# embedded.net
KiCad netlist of a schematic drawn in EAGLE
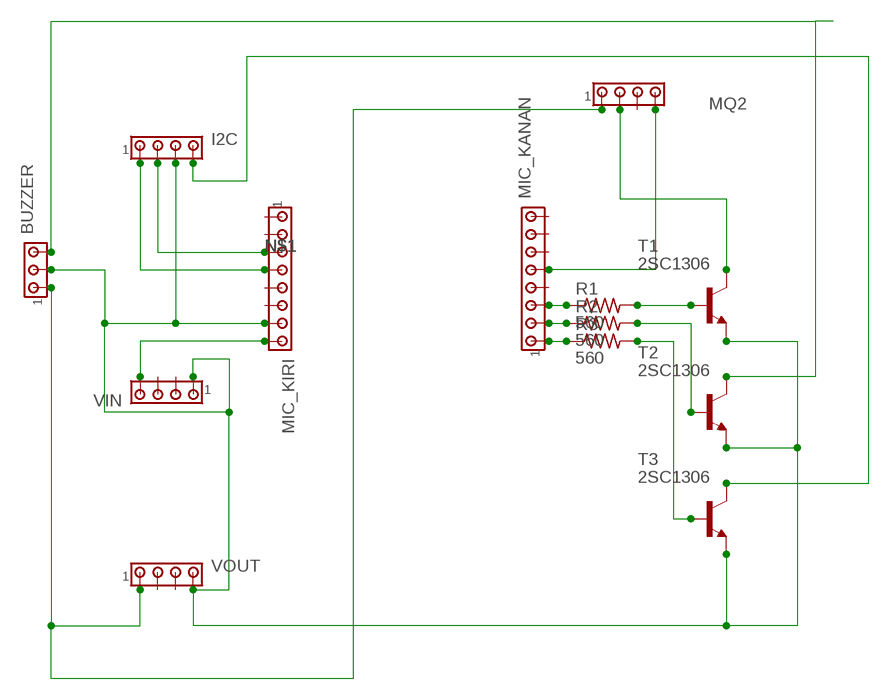
[diagram p0: schematic, sheet 1]

(export (version "E")
  (design (tool "Eeschema 10.0.6"))
  (components
    (comp (ref "BUZZER")
      (value "MTA03-100")
      (footprint "eagle-import:10X03MTA")
      (libsource (lib "eagle-import") (part "MTA03-100"))
    )
    (comp (ref "I2C")
      (value "MTA04-100")
      (footprint "eagle-import:10X04MTA")
      (libsource (lib "eagle-import") (part "MTA04-100"))
    )
    (comp (ref "MIC_KANAN")
      (value "MTA08-100")
      (footprint "eagle-import:10X08MTA")
      (libsource (lib "eagle-import") (part "MTA08-100"))
    )
    (comp (ref "MIC_KIRI")
      (value "MTA08-100")
      (footprint "eagle-import:10X08MTA")
      (libsource (lib "eagle-import") (part "MTA08-100"))
    )
    (comp (ref "MQ2")
      (value "MTA04-100")
      (footprint "eagle-import:10X04MTA")
      (libsource (lib "eagle-import") (part "MTA04-100"))
    )
    (comp (ref "R1")
      (value "560")
      (footprint "eagle-import:0204_7")
      (libsource (lib "eagle-import") (part "R-US_0204/7"))
    )
    (comp (ref "R2")
      (value "560")
      (footprint "eagle-import:0204_7")
      (libsource (lib "eagle-import") (part "R-US_0204/7"))
    )
    (comp (ref "R3")
      (value "560")
      (footprint "eagle-import:0204_7")
      (libsource (lib "eagle-import") (part "R-US_0204/7"))
    )
    (comp (ref "T1")
      (value "2SC1306")
      (footprint "eagle-import:TO220BV")
      (libsource (lib "eagle-import") (part "2SC1306"))
    )
    (comp (ref "T2")
      (value "2SC1306")
      (footprint "eagle-import:TO220BV")
      (libsource (lib "eagle-import") (part "2SC1306"))
    )
    (comp (ref "T3")
      (value "2SC1306")
      (footprint "eagle-import:TO220BV")
      (libsource (lib "eagle-import") (part "2SC1306"))
    )
    (comp (ref "VIN")
      (value "MTA04-100")
      (footprint "eagle-import:10X04MTA")
      (libsource (lib "eagle-import") (part "MTA04-100"))
    )
    (comp (ref "VOUT")
      (value "MTA04-100")
      (footprint "eagle-import:10X04MTA")
      (libsource (lib "eagle-import") (part "MTA04-100"))
    )
  )
  (nets
    (net (code "1") (name "/N$1") (class "Default")
      (node (ref "I2C") (pin "2") (pinfunction "2_2") (pintype "passive"))
      (node (ref "MIC_KIRI") (pin "3") (pinfunction "3_3") (pintype "passive"))
    )
    (net (code "2") (name "Net-(BUZZER-Pad1)") (class "Default")
      (node (ref "BUZZER") (pin "1") (pinfunction "1_1") (pintype "passive"))
      (node (ref "MQ2") (pin "1") (pinfunction "1_1") (pintype "passive"))
      (node (ref "VOUT") (pin "1") (pinfunction "1_1") (pintype "passive"))
    )
    (net (code "3") (name "Net-(I2C-Pad1)") (class "Default")
      (node (ref "I2C") (pin "1") (pinfunction "1_1") (pintype "passive"))
      (node (ref "MIC_KIRI") (pin "4") (pinfunction "4_4") (pintype "passive"))
    )
    (net (code "4") (name "Net-(MIC_KANAN-Pad1)") (class "Default")
      (node (ref "MIC_KANAN") (pin "1") (pinfunction "1_1") (pintype "passive"))
      (node (ref "R3") (pin "1") (pinfunction "1_1") (pintype "passive"))
    )
    (net (code "5") (name "Net-(MIC_KANAN-Pad2)") (class "Default")
      (node (ref "MIC_KANAN") (pin "2") (pinfunction "2_2") (pintype "passive"))
      (node (ref "R2") (pin "1") (pinfunction "1_1") (pintype "passive"))
    )
    (net (code "6") (name "Net-(MIC_KANAN-Pad3)") (class "Default")
      (node (ref "MIC_KANAN") (pin "3") (pinfunction "3_3") (pintype "passive"))
      (node (ref "R1") (pin "1") (pinfunction "1_1") (pintype "passive"))
    )
    (net (code "7") (name "Net-(MIC_KANAN-Pad5)") (class "Default")
      (node (ref "MIC_KANAN") (pin "5") (pinfunction "5_5") (pintype "passive"))
      (node (ref "MQ2") (pin "4") (pinfunction "4_4") (pintype "passive"))
    )
    (net (code "8") (name "Net-(MIC_KIRI-Pad8)") (class "Default")
      (node (ref "MIC_KIRI") (pin "8") (pinfunction "8_8") (pintype "passive"))
      (node (ref "VIN") (pin "4") (pinfunction "4_4") (pintype "passive"))
    )
    (net (code "9") (name "Net-(T1-B)") (class "Default")
      (node (ref "R1") (pin "2") (pinfunction "2_2") (pintype "passive"))
      (node (ref "T1") (pin "1") (pinfunction "B_1") (pintype "passive"))
    )
    (net (code "10") (name "Net-(T1-C)") (class "Default")
      (node (ref "MQ2") (pin "2") (pinfunction "2_2") (pintype "passive"))
      (node (ref "T1") (pin "2") (pinfunction "C_2") (pintype "passive"))
    )
    (net (code "11") (name "Net-(T1-E)") (class "Default")
      (node (ref "BUZZER") (pin "2") (pinfunction "2_2") (pintype "passive"))
      (node (ref "I2C") (pin "3") (pinfunction "3_3") (pintype "passive"))
      (node (ref "MIC_KIRI") (pin "7") (pinfunction "7_7") (pintype "passive"))
      (node (ref "T1") (pin "3") (pinfunction "E_3") (pintype "passive"))
      (node (ref "T2") (pin "3") (pinfunction "E_3") (pintype "passive"))
      (node (ref "T3") (pin "3") (pinfunction "E_3") (pintype "passive"))
      (node (ref "VIN") (pin "1") (pinfunction "1_1") (pintype "passive"))
      (node (ref "VOUT") (pin "4") (pinfunction "4_4") (pintype "passive"))
    )
    (net (code "12") (name "Net-(T2-B)") (class "Default")
      (node (ref "R2") (pin "2") (pinfunction "2_2") (pintype "passive"))
      (node (ref "T2") (pin "1") (pinfunction "B_1") (pintype "passive"))
    )
    (net (code "13") (name "Net-(T2-C)") (class "Default")
      (node (ref "BUZZER") (pin "3") (pinfunction "3_3") (pintype "passive"))
      (node (ref "T2") (pin "2") (pinfunction "C_2") (pintype "passive"))
    )
    (net (code "14") (name "Net-(T3-B)") (class "Default")
      (node (ref "R3") (pin "2") (pinfunction "2_2") (pintype "passive"))
      (node (ref "T3") (pin "1") (pinfunction "B_1") (pintype "passive"))
    )
    (net (code "15") (name "Net-(T3-C)") (class "Default")
      (node (ref "I2C") (pin "4") (pinfunction "4_4") (pintype "passive"))
      (node (ref "T3") (pin "2") (pinfunction "C_2") (pintype "passive"))
    )
    (net (code "16") (name "unconnected-(MIC_KANAN-Pad4)") (class "Default")
      (node (ref "MIC_KANAN") (pin "4") (pinfunction "4_4") (pintype "passive"))
    )
    (net (code "17") (name "unconnected-(MIC_KANAN-Pad6)") (class "Default")
      (node (ref "MIC_KANAN") (pin "6") (pinfunction "6_6") (pintype "passive"))
    )
    (net (code "18") (name "unconnected-(MIC_KANAN-Pad7)") (class "Default")
      (node (ref "MIC_KANAN") (pin "7") (pinfunction "7_7") (pintype "passive"))
    )
    (net (code "19") (name "unconnected-(MIC_KANAN-Pad8)") (class "Default")
      (node (ref "MIC_KANAN") (pin "8") (pinfunction "8_8") (pintype "passive"))
    )
    (net (code "20") (name "unconnected-(MIC_KIRI-Pad1)") (class "Default")
      (node (ref "MIC_KIRI") (pin "1") (pinfunction "1_1") (pintype "passive"))
    )
    (net (code "21") (name "unconnected-(MIC_KIRI-Pad2)") (class "Default")
      (node (ref "MIC_KIRI") (pin "2") (pinfunction "2_2") (pintype "passive"))
    )
    (net (code "22") (name "unconnected-(MIC_KIRI-Pad5)") (class "Default")
      (node (ref "MIC_KIRI") (pin "5") (pinfunction "5_5") (pintype "passive"))
    )
    (net (code "23") (name "unconnected-(MIC_KIRI-Pad6)") (class "Default")
      (node (ref "MIC_KIRI") (pin "6") (pinfunction "6_6") (pintype "passive"))
    )
    (net (code "24") (name "unconnected-(MQ2-Pad3)") (class "Default")
      (node (ref "MQ2") (pin "3") (pinfunction "3_3") (pintype "passive"))
    )
    (net (code "25") (name "unconnected-(VIN-Pad2)") (class "Default")
      (node (ref "VIN") (pin "2") (pinfunction "2_2") (pintype "passive"))
    )
    (net (code "26") (name "unconnected-(VIN-Pad3)") (class "Default")
      (node (ref "VIN") (pin "3") (pinfunction "3_3") (pintype "passive"))
    )
    (net (code "27") (name "unconnected-(VOUT-Pad2)") (class "Default")
      (node (ref "VOUT") (pin "2") (pinfunction "2_2") (pintype "passive"))
    )
    (net (code "28") (name "unconnected-(VOUT-Pad3)") (class "Default")
      (node (ref "VOUT") (pin "3") (pinfunction "3_3") (pintype "passive"))
    )
  )
)
